# control.net
KiCad netlist of a schematic drawn in EAGLE
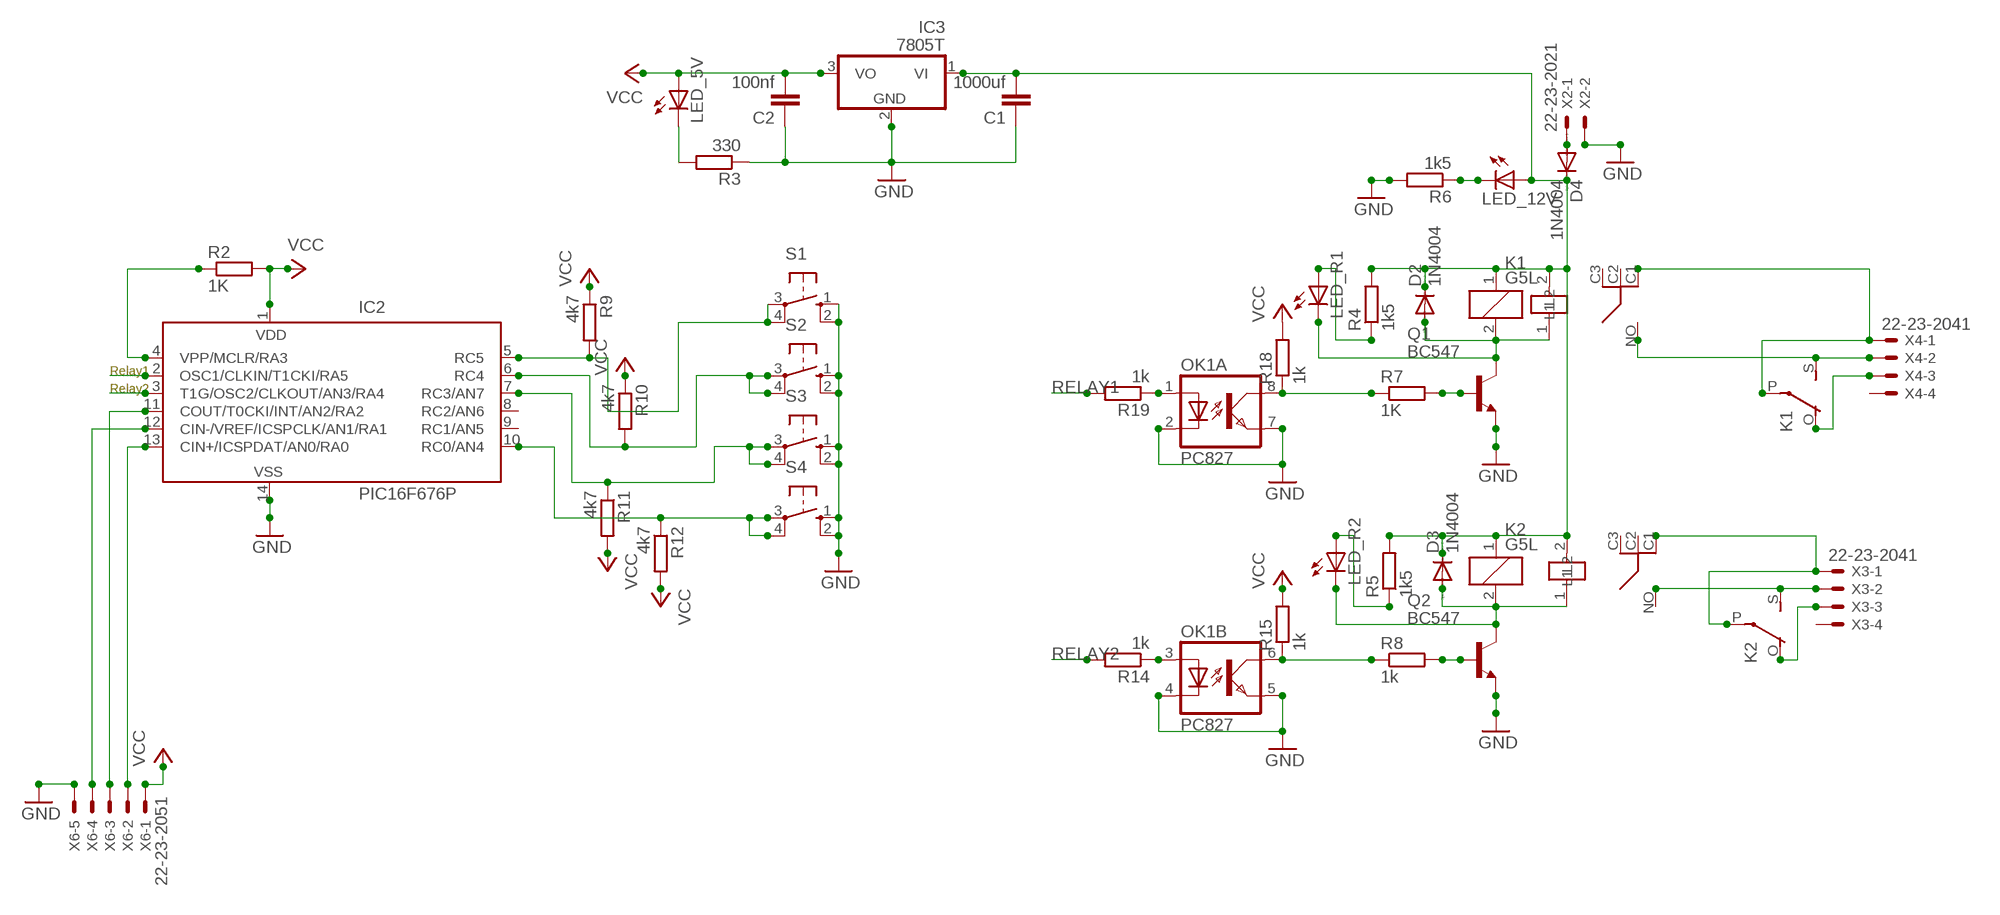
[diagram p0: schematic, sheet 1]

(export (version "E")
  (design (tool "Eeschema 10.0.6"))
  (components
    (comp (ref "C1")
      (value "1000uf")
      (footprint "eagle-import:C5B2.5")
      (libsource (lib "eagle-import") (part "C5/2.5"))
    )
    (comp (ref "C2")
      (value "100nf")
      (footprint "eagle-import:C2.5-6")
      (libsource (lib "eagle-import") (part "C2.5/6"))
    )
    (comp (ref "D2")
      (value "1N4004")
      (footprint "eagle-import:DO41-10")
      (libsource (lib "eagle-import") (part "1N4004"))
    )
    (comp (ref "D3")
      (value "1N4004")
      (footprint "eagle-import:DO41-10")
      (libsource (lib "eagle-import") (part "1N4004"))
    )
    (comp (ref "D4")
      (value "1N4004")
      (footprint "eagle-import:DO41-10")
      (libsource (lib "eagle-import") (part "1N4004"))
    )
    (comp (ref "IC2")
      (value "PIC16F676P")
      (footprint "eagle-import:DIL14")
      (fields (field (name "MF") "MICROCHIP") (field (name "MPN") "PIC16F676-I/P"))
      (libsource (lib "eagle-import") (part "PIC16F676P"))
    )
    (comp (ref "IC3")
      (value "7805T")
      (footprint "eagle-import:TO220H")
      (libsource (lib "eagle-import") (part "78T05"))
    )
    (comp (ref "K1")
      (value "G5L")
      (footprint "eagle-import:G5LE")
      (libsource (lib "eagle-import") (part "G5L"))
    )
    (comp (ref "K2")
      (value "G5L")
      (footprint "eagle-import:G5LE")
      (libsource (lib "eagle-import") (part "G5L"))
    )
    (comp (ref "LED_5V")
      (value "LED3MM")
      (footprint "eagle-import:LED3MM")
      (libsource (lib "eagle-import") (part "LED3MM"))
    )
    (comp (ref "LED_12V")
      (value "LED3MM")
      (footprint "eagle-import:LED3MM")
      (libsource (lib "eagle-import") (part "LED3MM"))
    )
    (comp (ref "LED_R1")
      (value "LED3MM")
      (footprint "eagle-import:LED3MM")
      (libsource (lib "eagle-import") (part "LED3MM"))
    )
    (comp (ref "LED_R2")
      (value "LED3MM")
      (footprint "eagle-import:LED3MM")
      (libsource (lib "eagle-import") (part "LED3MM"))
    )
    (comp (ref "OK1")
      (value "PC827")
      (footprint "eagle-import:DIL08")
      (libsource (lib "eagle-import") (part "PC827"))
    )
    (comp (ref "Q1")
      (value "BC547")
      (footprint "eagle-import:TO92-EBC")
      (libsource (lib "eagle-import") (part "BC548"))
    )
    (comp (ref "Q2")
      (value "BC547")
      (footprint "eagle-import:TO92-EBC")
      (libsource (lib "eagle-import") (part "BC548"))
    )
    (comp (ref "R2")
      (value "1K")
      (footprint "eagle-import:0207_10")
      (libsource (lib "eagle-import") (part "R-EU_0207/10"))
    )
    (comp (ref "R3")
      (value "330")
      (footprint "eagle-import:0207_10")
      (libsource (lib "eagle-import") (part "R-EU_0207/10"))
    )
    (comp (ref "R4")
      (value "1k5")
      (footprint "eagle-import:0207_10")
      (libsource (lib "eagle-import") (part "R-EU_0207/10"))
    )
    (comp (ref "R5")
      (value "1k5")
      (footprint "eagle-import:0207_10")
      (libsource (lib "eagle-import") (part "R-EU_0207/10"))
    )
    (comp (ref "R6")
      (value "1k5")
      (footprint "eagle-import:0207_10")
      (libsource (lib "eagle-import") (part "R-EU_0207/10"))
    )
    (comp (ref "R7")
      (value "1K")
      (footprint "eagle-import:0207_10")
      (libsource (lib "eagle-import") (part "R-EU_0207/10"))
    )
    (comp (ref "R8")
      (value "1k")
      (footprint "eagle-import:0207_10")
      (libsource (lib "eagle-import") (part "R-EU_0207/10"))
    )
    (comp (ref "R9")
      (value "4k7")
      (footprint "eagle-import:0207_10")
      (libsource (lib "eagle-import") (part "R-EU_0207/10"))
    )
    (comp (ref "R10")
      (value "4k7")
      (footprint "eagle-import:0207_10")
      (libsource (lib "eagle-import") (part "R-EU_0207/10"))
    )
    (comp (ref "R11")
      (value "4k7")
      (footprint "eagle-import:0207_10")
      (libsource (lib "eagle-import") (part "R-EU_0207/10"))
    )
    (comp (ref "R12")
      (value "4k7")
      (footprint "eagle-import:0207_10")
      (libsource (lib "eagle-import") (part "R-EU_0207/10"))
    )
    (comp (ref "R14")
      (value "1k")
      (footprint "eagle-import:0207_10")
      (libsource (lib "eagle-import") (part "R-EU_0207/10"))
    )
    (comp (ref "R15")
      (value "1k")
      (footprint "eagle-import:0207_10")
      (libsource (lib "eagle-import") (part "R-EU_0207/10"))
    )
    (comp (ref "R18")
      (value "1k")
      (footprint "eagle-import:0207_10")
      (libsource (lib "eagle-import") (part "R-EU_0207/10"))
    )
    (comp (ref "R19")
      (value "1k")
      (footprint "eagle-import:0207_10")
      (libsource (lib "eagle-import") (part "R-EU_0207/10"))
    )
    (comp (ref "S1")
      (value "40-XX")
      (footprint "eagle-import:B3F-40XX")
      (fields (field (name "MF") "OMRON COMPONENTS USA") (field (name "MPN") "B3F-4000"))
      (libsource (lib "eagle-import") (part "40-XX"))
    )
    (comp (ref "S2")
      (value "40-XX")
      (footprint "eagle-import:B3F-40XX")
      (fields (field (name "MF") "OMRON COMPONENTS USA") (field (name "MPN") "B3F-4000"))
      (libsource (lib "eagle-import") (part "40-XX"))
    )
    (comp (ref "S3")
      (value "40-XX")
      (footprint "eagle-import:B3F-40XX")
      (fields (field (name "MF") "OMRON COMPONENTS USA") (field (name "MPN") "B3F-4000"))
      (libsource (lib "eagle-import") (part "40-XX"))
    )
    (comp (ref "S4")
      (value "40-XX")
      (footprint "eagle-import:B3F-40XX")
      (fields (field (name "MF") "OMRON COMPONENTS USA") (field (name "MPN") "B3F-4000"))
      (libsource (lib "eagle-import") (part "40-XX"))
    )
    (comp (ref "U$1")
      (value "RL703")
      (footprint "eagle-import:RL703")
      (libsource (lib "eagle-import") (part "RL703"))
    )
    (comp (ref "U$2")
      (value "RL703")
      (footprint "eagle-import:RL703")
      (libsource (lib "eagle-import") (part "RL703"))
    )
    (comp (ref "X2")
      (value "22-23-2021")
      (footprint "eagle-import:22-23-2021")
      (fields (field (name "MF") "MOLEX"))
      (libsource (lib "eagle-import") (part "22-23-2021"))
    )
    (comp (ref "X3")
      (value "22-23-2041")
      (footprint "eagle-import:22-23-2041")
      (fields (field (name "MF") "MOLEX"))
      (libsource (lib "eagle-import") (part "22-23-2041"))
    )
    (comp (ref "X4")
      (value "22-23-2041")
      (footprint "eagle-import:22-23-2041")
      (fields (field (name "MF") "MOLEX"))
      (libsource (lib "eagle-import") (part "22-23-2041"))
    )
    (comp (ref "X6")
      (value "22-23-2051")
      (footprint "eagle-import:22-23-2051")
      (fields (field (name "MF") "MOLEX"))
      (libsource (lib "eagle-import") (part "22-23-2051"))
    )
  )
  (nets
    (net (code "1") (name "/RELAY1") (class "Default")
      (node (ref "IC2") (pin "2") (pinfunction "OSC1/CLKIN/T1CKI/RA5_2") (pintype "bidirectional"))
      (node (ref "R19") (pin "2") (pinfunction "2_2") (pintype "passive"))
    )
    (net (code "2") (name "/RELAY2") (class "Default")
      (node (ref "IC2") (pin "3") (pinfunction "T1G/OSC2/CLKOUT/AN3/RA4_3") (pintype "bidirectional"))
      (node (ref "R14") (pin "2") (pinfunction "2_2") (pintype "passive"))
    )
    (net (code "3") (name "GND") (class "Default")
      (node (ref "C1") (pin "1") (pinfunction "1_1") (pintype "passive"))
      (node (ref "C2") (pin "1") (pinfunction "1_1") (pintype "passive"))
      (node (ref "IC2") (pin "14") (pinfunction "VSS_14") (pintype "power_in"))
      (node (ref "IC3") (pin "2") (pinfunction "GND_2") (pintype "passive"))
      (node (ref "OK1") (pin "2") (pinfunction "C_2") (pintype "passive"))
      (node (ref "OK1") (pin "4") (pinfunction "C_4") (pintype "passive"))
      (node (ref "OK1") (pin "5") (pinfunction "EMIT_5") (pintype "passive"))
      (node (ref "OK1") (pin "7") (pinfunction "EMIT_7") (pintype "passive"))
      (node (ref "Q1") (pin "E") (pinfunction "E_E") (pintype "passive"))
      (node (ref "Q2") (pin "E") (pinfunction "E_E") (pintype "passive"))
      (node (ref "R3") (pin "1") (pinfunction "1_1") (pintype "passive"))
      (node (ref "R6") (pin "2") (pinfunction "2_2") (pintype "passive"))
      (node (ref "S1") (pin "1") (pinfunction "S_1") (pintype "passive"))
      (node (ref "S1") (pin "2") (pinfunction "S1_2") (pintype "passive"))
      (node (ref "S2") (pin "1") (pinfunction "S_1") (pintype "passive"))
      (node (ref "S2") (pin "2") (pinfunction "S1_2") (pintype "passive"))
      (node (ref "S3") (pin "1") (pinfunction "S_1") (pintype "passive"))
      (node (ref "S3") (pin "2") (pinfunction "S1_2") (pintype "passive"))
      (node (ref "S4") (pin "1") (pinfunction "S_1") (pintype "passive"))
      (node (ref "S4") (pin "2") (pinfunction "S1_2") (pintype "passive"))
      (node (ref "X2") (pin "2") (pinfunction "S_2") (pintype "passive"))
      (node (ref "X6") (pin "5") (pinfunction "S_5") (pintype "passive"))
    )
    (net (code "4") (name "Net-(IC2-CIN+{slash}ICSPDAT{slash}AN0{slash}RA0)") (class "Default")
      (node (ref "IC2") (pin "13") (pinfunction "CIN+/ICSPDAT/AN0/RA0_13") (pintype "bidirectional"))
      (node (ref "X6") (pin "2") (pinfunction "S_2") (pintype "passive"))
    )
    (net (code "5") (name "Net-(IC2-CIN-{slash}VREF{slash}ICSPCLK{slash}AN1{slash}RA1)") (class "Default")
      (node (ref "IC2") (pin "12") (pinfunction "CIN-/VREF/ICSPCLK/AN1/RA1_12") (pintype "bidirectional"))
      (node (ref "X6") (pin "4") (pinfunction "S_4") (pintype "passive"))
    )
    (net (code "6") (name "Net-(IC2-COUT{slash}T0CKI{slash}INT{slash}AN2{slash}RA2)") (class "Default")
      (node (ref "IC2") (pin "11") (pinfunction "COUT/T0CKI/INT/AN2/RA2_11") (pintype "bidirectional"))
      (node (ref "X6") (pin "3") (pinfunction "S_3") (pintype "passive"))
    )
    (net (code "7") (name "Net-(IC2-RC0{slash}AN4)") (class "Default")
      (node (ref "IC2") (pin "10") (pinfunction "RC0/AN4_10") (pintype "bidirectional"))
      (node (ref "R12") (pin "1") (pinfunction "1_1") (pintype "passive"))
      (node (ref "S4") (pin "3") (pinfunction "P_3") (pintype "passive"))
      (node (ref "S4") (pin "4") (pinfunction "P1_4") (pintype "passive"))
    )
    (net (code "8") (name "Net-(IC2-RC3{slash}AN7)") (class "Default")
      (node (ref "IC2") (pin "7") (pinfunction "RC3/AN7_7") (pintype "bidirectional"))
      (node (ref "R11") (pin "1") (pinfunction "1_1") (pintype "passive"))
      (node (ref "S3") (pin "3") (pinfunction "P_3") (pintype "passive"))
      (node (ref "S3") (pin "4") (pinfunction "P1_4") (pintype "passive"))
    )
    (net (code "9") (name "Net-(IC2-RC4)") (class "Default")
      (node (ref "IC2") (pin "6") (pinfunction "RC4_6") (pintype "bidirectional"))
      (node (ref "R10") (pin "2") (pinfunction "2_2") (pintype "passive"))
      (node (ref "S2") (pin "3") (pinfunction "P_3") (pintype "passive"))
      (node (ref "S2") (pin "4") (pinfunction "P1_4") (pintype "passive"))
    )
    (net (code "10") (name "Net-(IC2-RC5)") (class "Default")
      (node (ref "IC2") (pin "5") (pinfunction "RC5_5") (pintype "bidirectional"))
      (node (ref "R9") (pin "2") (pinfunction "2_2") (pintype "passive"))
      (node (ref "S1") (pin "3") (pinfunction "P_3") (pintype "passive"))
      (node (ref "S1") (pin "4") (pinfunction "P1_4") (pintype "passive"))
    )
    (net (code "11") (name "Net-(IC2-VPP{slash}MCLR{slash}RA3)") (class "Default")
      (node (ref "IC2") (pin "4") (pinfunction "VPP/MCLR/RA3_4") (pintype "input"))
      (node (ref "R2") (pin "1") (pinfunction "1_1") (pintype "passive"))
    )
    (net (code "12") (name "Net-(IC3-VI)") (class "Default")
      (node (ref "C1") (pin "2") (pinfunction "2_2") (pintype "passive"))
      (node (ref "D2") (pin "C") (pinfunction "C_C") (pintype "passive"))
      (node (ref "D3") (pin "C") (pinfunction "C_C") (pintype "passive"))
      (node (ref "D4") (pin "C") (pinfunction "C_C") (pintype "passive"))
      (node (ref "IC3") (pin "1") (pinfunction "VI_1") (pintype "input"))
      (node (ref "K1") (pin "1") (pinfunction "1_1") (pintype "passive"))
      (node (ref "K2") (pin "1") (pinfunction "1_1") (pintype "passive"))
      (node (ref "LED_12V") (pin "A") (pinfunction "A_A") (pintype "passive"))
      (node (ref "R4") (pin "2") (pinfunction "2_2") (pintype "passive"))
      (node (ref "R5") (pin "2") (pinfunction "2_2") (pintype "passive"))
      (node (ref "U$1") (pin "2") (pinfunction "L1_2") (pintype "bidirectional"))
      (node (ref "U$2") (pin "2") (pinfunction "L1_2") (pintype "bidirectional"))
    )
    (net (code "13") (name "Net-(LED_5V-C)") (class "Default")
      (node (ref "LED_5V") (pin "K") (pinfunction "C_K") (pintype "passive"))
      (node (ref "R3") (pin "2") (pinfunction "2_2") (pintype "passive"))
    )
    (net (code "14") (name "Net-(LED_12V-C)") (class "Default")
      (node (ref "LED_12V") (pin "K") (pinfunction "C_K") (pintype "passive"))
      (node (ref "R6") (pin "1") (pinfunction "1_1") (pintype "passive"))
    )
    (net (code "15") (name "Net-(LED_R1-C)") (class "Default")
      (node (ref "D2") (pin "A") (pinfunction "A_A") (pintype "passive"))
      (node (ref "K1") (pin "2") (pinfunction "2_2") (pintype "passive"))
      (node (ref "LED_R1") (pin "K") (pinfunction "C_K") (pintype "passive"))
      (node (ref "Q1") (pin "C") (pinfunction "C_C") (pintype "passive"))
      (node (ref "U$1") (pin "1") (pinfunction "L2_1") (pintype "bidirectional"))
    )
    (net (code "16") (name "Net-(LED_R1-PadA)") (class "Default")
      (node (ref "LED_R1") (pin "A") (pinfunction "A_A") (pintype "passive"))
      (node (ref "R4") (pin "1") (pinfunction "1_1") (pintype "passive"))
    )
    (net (code "17") (name "Net-(LED_R2-C)") (class "Default")
      (node (ref "D3") (pin "A") (pinfunction "A_A") (pintype "passive"))
      (node (ref "K2") (pin "2") (pinfunction "2_2") (pintype "passive"))
      (node (ref "LED_R2") (pin "K") (pinfunction "C_K") (pintype "passive"))
      (node (ref "Q2") (pin "C") (pinfunction "C_C") (pintype "passive"))
      (node (ref "U$2") (pin "1") (pinfunction "L2_1") (pintype "bidirectional"))
    )
    (net (code "18") (name "Net-(LED_R2-PadA)") (class "Default")
      (node (ref "LED_R2") (pin "A") (pinfunction "A_A") (pintype "passive"))
      (node (ref "R5") (pin "1") (pinfunction "1_1") (pintype "passive"))
    )
    (net (code "19") (name "Net-(OK1A-A)") (class "Default")
      (node (ref "OK1") (pin "1") (pinfunction "A_1") (pintype "passive"))
      (node (ref "R19") (pin "1") (pinfunction "1_1") (pintype "passive"))
    )
    (net (code "20") (name "Net-(OK1A-COL)") (class "Default")
      (node (ref "OK1") (pin "8") (pinfunction "COL_8") (pintype "passive"))
      (node (ref "R18") (pin "1") (pinfunction "1_1") (pintype "passive"))
      (node (ref "R7") (pin "1") (pinfunction "1_1") (pintype "passive"))
    )
    (net (code "21") (name "Net-(OK1B-A)") (class "Default")
      (node (ref "OK1") (pin "3") (pinfunction "A_3") (pintype "passive"))
      (node (ref "R14") (pin "1") (pinfunction "1_1") (pintype "passive"))
    )
    (net (code "22") (name "Net-(OK1B-COL)") (class "Default")
      (node (ref "OK1") (pin "6") (pinfunction "COL_6") (pintype "passive"))
      (node (ref "R15") (pin "1") (pinfunction "1_1") (pintype "passive"))
      (node (ref "R8") (pin "1") (pinfunction "1_1") (pintype "passive"))
    )
    (net (code "23") (name "Net-(Q1-PadB)") (class "Default")
      (node (ref "Q1") (pin "B") (pinfunction "B_B") (pintype "passive"))
      (node (ref "R7") (pin "2") (pinfunction "2_2") (pintype "passive"))
    )
    (net (code "24") (name "Net-(Q2-PadB)") (class "Default")
      (node (ref "Q2") (pin "B") (pinfunction "B_B") (pintype "passive"))
      (node (ref "R8") (pin "2") (pinfunction "2_2") (pintype "passive"))
    )
    (net (code "25") (name "Net-(X2A-S)") (class "Default")
      (node (ref "D4") (pin "A") (pinfunction "A_A") (pintype "passive"))
      (node (ref "X2") (pin "1") (pinfunction "S_1") (pintype "passive"))
    )
    (net (code "26") (name "Net-(X3A-S)") (class "Default")
      (node (ref "K2") (pin "P") (pinfunction "P_P") (pintype "passive"))
      (node (ref "U$2") (pin "C1") (pinfunction "C1_C1") (pintype "bidirectional"))
      (node (ref "X3") (pin "1") (pinfunction "S_1") (pintype "passive"))
    )
    (net (code "27") (name "Net-(X3B-S)") (class "Default")
      (node (ref "K2") (pin "S") (pinfunction "S_S") (pintype "passive"))
      (node (ref "X3") (pin "2") (pinfunction "S_2") (pintype "passive"))
    )
    (net (code "28") (name "Net-(X3C-S)") (class "Default")
      (node (ref "K2") (pin "O") (pinfunction "O_O") (pintype "passive"))
      (node (ref "X3") (pin "3") (pinfunction "S_3") (pintype "passive"))
    )
    (net (code "29") (name "Net-(X4A-S)") (class "Default")
      (node (ref "K1") (pin "P") (pinfunction "P_P") (pintype "passive"))
      (node (ref "U$1") (pin "C1") (pinfunction "C1_C1") (pintype "bidirectional"))
      (node (ref "X4") (pin "1") (pinfunction "S_1") (pintype "passive"))
    )
    (net (code "30") (name "Net-(X4B-S)") (class "Default")
      (node (ref "K1") (pin "S") (pinfunction "S_S") (pintype "passive"))
      (node (ref "U$1") (pin "NO") (pinfunction "NO_NO") (pintype "bidirectional"))
      (node (ref "X4") (pin "2") (pinfunction "S_2") (pintype "passive"))
    )
    (net (code "31") (name "Net-(X4C-S)") (class "Default")
      (node (ref "K1") (pin "O") (pinfunction "O_O") (pintype "passive"))
      (node (ref "X4") (pin "3") (pinfunction "S_3") (pintype "passive"))
    )
    (net (code "32") (name "VCC") (class "Default")
      (node (ref "C2") (pin "2") (pinfunction "2_2") (pintype "passive"))
      (node (ref "IC2") (pin "1") (pinfunction "VDD_1") (pintype "power_in"))
      (node (ref "IC3") (pin "3") (pinfunction "VO_3") (pintype "passive"))
      (node (ref "LED_5V") (pin "A") (pinfunction "A_A") (pintype "passive"))
      (node (ref "R10") (pin "1") (pinfunction "1_1") (pintype "passive"))
      (node (ref "R11") (pin "2") (pinfunction "2_2") (pintype "passive"))
      (node (ref "R12") (pin "2") (pinfunction "2_2") (pintype "passive"))
      (node (ref "R15") (pin "2") (pinfunction "2_2") (pintype "passive"))
      (node (ref "R18") (pin "2") (pinfunction "2_2") (pintype "passive"))
      (node (ref "R2") (pin "2") (pinfunction "2_2") (pintype "passive"))
      (node (ref "R9") (pin "1") (pinfunction "1_1") (pintype "passive"))
      (node (ref "X6") (pin "1") (pinfunction "S_1") (pintype "passive"))
    )
    (net (code "33") (name "unconnected-(IC2-RC1{slash}AN5-Pad9)") (class "Default")
      (node (ref "IC2") (pin "9") (pinfunction "RC1/AN5_9") (pintype "bidirectional"))
    )
    (net (code "34") (name "unconnected-(IC2-RC2{slash}AN6-Pad8)") (class "Default")
      (node (ref "IC2") (pin "8") (pinfunction "RC2/AN6_8") (pintype "bidirectional"))
    )
    (net (code "35") (name "unconnected-(U$1-PadC2)") (class "Default")
      (node (ref "U$1") (pin "C2") (pinfunction "C2_C2") (pintype "bidirectional"))
    )
    (net (code "36") (name "unconnected-(U$1-PadC3)") (class "Default")
      (node (ref "U$1") (pin "C3") (pinfunction "C3_C3") (pintype "bidirectional"))
    )
    (net (code "37") (name "unconnected-(U$2-PadC2)") (class "Default")
      (node (ref "U$2") (pin "C2") (pinfunction "C2_C2") (pintype "bidirectional"))
    )
    (net (code "38") (name "unconnected-(U$2-PadC3)") (class "Default")
      (node (ref "U$2") (pin "C3") (pinfunction "C3_C3") (pintype "bidirectional"))
    )
    (net (code "39") (name "unconnected-(U$2-PadNO)") (class "Default")
      (node (ref "U$2") (pin "NO") (pinfunction "NO_NO") (pintype "bidirectional"))
    )
    (net (code "40") (name "unconnected-(X3D-S-Pad4)") (class "Default")
      (node (ref "X3") (pin "4") (pinfunction "S_4") (pintype "passive"))
    )
    (net (code "41") (name "unconnected-(X4D-S-Pad4)") (class "Default")
      (node (ref "X4") (pin "4") (pinfunction "S_4") (pintype "passive"))
    )
  )
)
